# E106.net
KiCad netlist of a schematic drawn in EAGLE
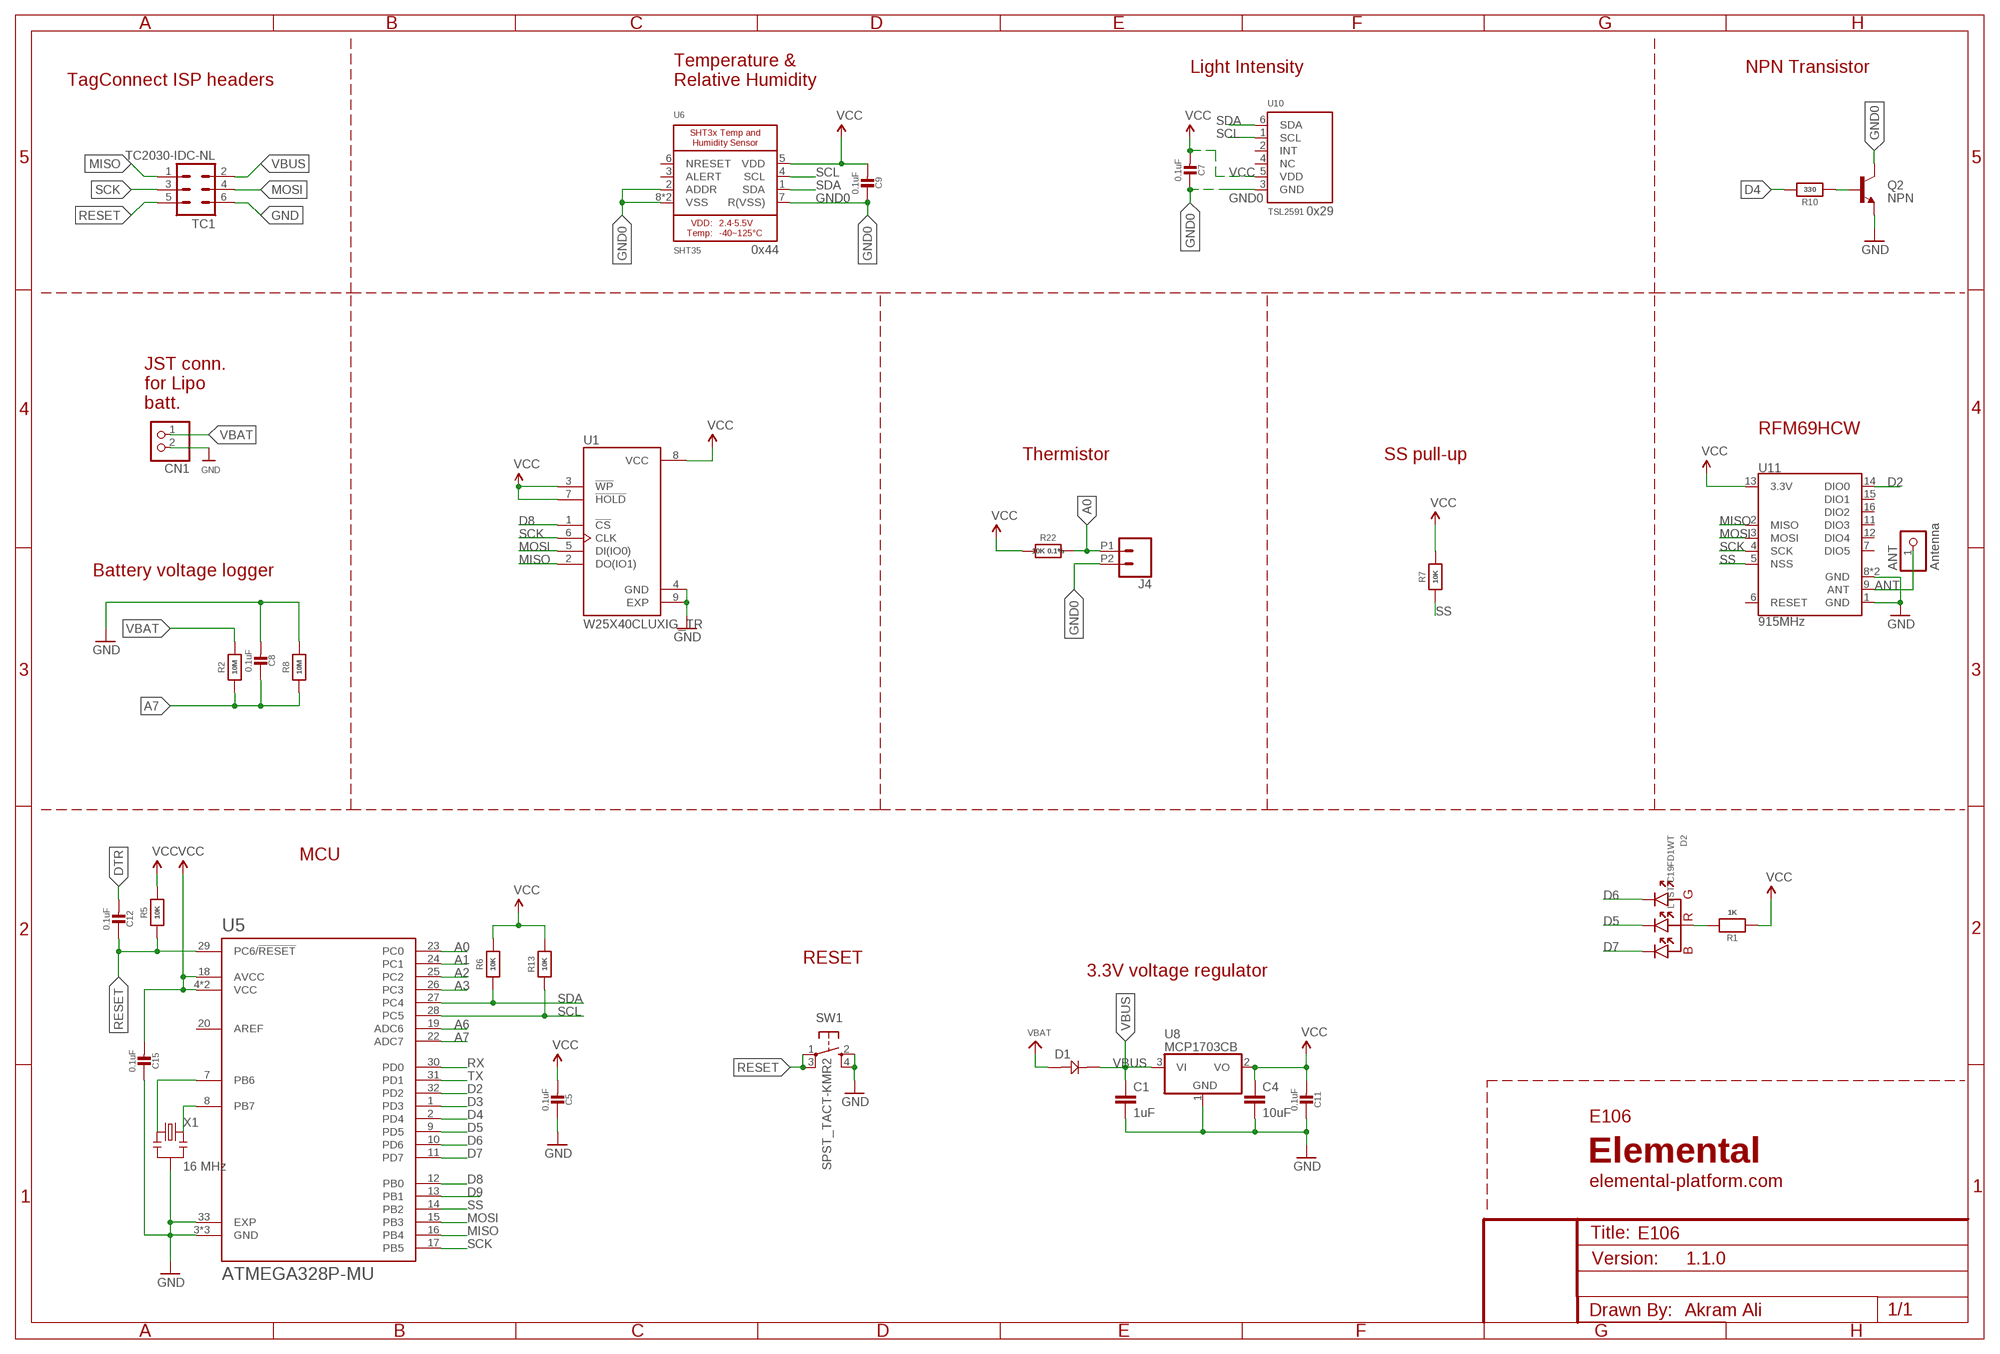
[diagram p0: schematic, sheet 1]

(export (version "E")
  (design (tool "Eeschema 10.0.6"))
  (components
    (comp (ref "ANT")
      (value "Antenna")
      (footprint "eagle-import:1X01-CLEANBIG")
      (fields (field (name "MPN") "Helical antenna"))
      (libsource (lib "eagle-import") (part "PINHD-1X1CB"))
    )
    (comp (ref "C1")
      (value "1uF")
      (footprint "eagle-import:0805")
      (fields (field (name "MPN") "CC0805ZRY5V8BB105"))
      (libsource (lib "eagle-import") (part "CAP0805"))
    )
    (comp (ref "C4")
      (value "10uF")
      (footprint "eagle-import:0805")
      (fields (field (name "MPN") "CC0805KKX5R6BB106"))
      (libsource (lib "eagle-import") (part "CAP0805"))
    )
    (comp (ref "C5")
      (value "0.1uF")
      (footprint "eagle-import:MICROBUILDER__0402MP")
      (fields (field (name "MPN") "GRM155R71C104KA88J"))
      (libsource (lib "eagle-import") (part "MICROBUILDER_CAP_CERAMIC_0402MP"))
    )
    (comp (ref "C7")
      (value "0.1uF")
      (footprint "eagle-import:MICROBUILDER__0402MP")
      (fields (field (name "MPN") "GRM155R71C104KA88J"))
      (libsource (lib "eagle-import") (part "MICROBUILDER_CAP_CERAMIC_0402MP"))
    )
    (comp (ref "C8")
      (value "0.1uF")
      (footprint "eagle-import:MICROBUILDER__0402MP")
      (fields (field (name "MPN") "GRM155R71C104KA88J"))
      (libsource (lib "eagle-import") (part "MICROBUILDER_CAP_CERAMIC_0402MP"))
    )
    (comp (ref "C9")
      (value "0.1uF")
      (footprint "eagle-import:MICROBUILDER__0402MP")
      (fields (field (name "MPN") "GRM155R71C104KA88J"))
      (libsource (lib "eagle-import") (part "MICROBUILDER_CAP_CERAMIC_0402MP"))
    )
    (comp (ref "C11")
      (value "0.1uF")
      (footprint "eagle-import:MICROBUILDER__0402MP")
      (fields (field (name "MPN") "GRM155R71C104KA88J"))
      (libsource (lib "eagle-import") (part "MICROBUILDER_CAP_CERAMIC_0402MP"))
    )
    (comp (ref "C12")
      (value "0.1uF")
      (footprint "eagle-import:MICROBUILDER__0402MP")
      (fields (field (name "MPN") "GRM155R71C104KA88J"))
      (libsource (lib "eagle-import") (part "MICROBUILDER_CAP_CERAMIC_0402MP"))
    )
    (comp (ref "C15")
      (value "0.1uF")
      (footprint "eagle-import:MICROBUILDER__0402MP")
      (fields (field (name "MPN") "GRM155R71C104KA88J"))
      (libsource (lib "eagle-import") (part "MICROBUILDER_CAP_CERAMIC_0402MP"))
    )
    (comp (ref "CN1")
      (value "JST_2PIN-SMT-RA")
      (footprint "eagle-import:JST-PH-2-SMT-RA")
      (libsource (lib "eagle-import") (part "JST_2PIN-SMT-RA"))
    )
    (comp (ref "D1")
      (value "DIODE_SCHOTTKY0805-RES")
      (footprint "eagle-import:0805")
      (libsource (lib "eagle-import") (part "DIODE_SCHOTTKY0805-RES"))
    )
    (comp (ref "D2")
      (value "LTST-C19FD1WT")
      (footprint "eagle-import:4-SMD")
      (fields (field (name "MF") "Lite-On Inc."))
      (libsource (lib "eagle-import") (part "LTST-C19FD1WT"))
    )
    (comp (ref "J4")
      (value "CONN_022.54MM_SCREWTERM")
      (footprint "eagle-import:1X02_2.54_SCREWTERM")
      (libsource (lib "eagle-import") (part "CONN_022.54MM_SCREWTERM"))
    )
    (comp (ref "Q2")
      (value "NPN")
      (footprint "eagle-import:SOT23-3@1")
      (libsource (lib "eagle-import") (part "TRANSISTOR_NPNMMBT5088"))
    )
    (comp (ref "R1")
      (value "1K")
      (footprint "eagle-import:MICROBUILDER__0402MP")
      (fields (field (name "MPN") "RC0402JR-0710KL"))
      (libsource (lib "eagle-import") (part "MICROBUILDER_RESISTOR_0402MP"))
    )
    (comp (ref "R2")
      (value "10M")
      (footprint "eagle-import:MICROBUILDER__0402MP")
      (fields (field (name "MPN") "RC0402JR-0710KL"))
      (libsource (lib "eagle-import") (part "MICROBUILDER_RESISTOR_0402MP"))
    )
    (comp (ref "R5")
      (value "10K")
      (footprint "eagle-import:MICROBUILDER__0402MP")
      (fields (field (name "MPN") "RC0402JR-0710KL"))
      (libsource (lib "eagle-import") (part "MICROBUILDER_RESISTOR_0402MP"))
    )
    (comp (ref "R6")
      (value "10K")
      (footprint "eagle-import:MICROBUILDER__0402MP")
      (fields (field (name "MPN") "RC0402JR-0710KL"))
      (libsource (lib "eagle-import") (part "MICROBUILDER_RESISTOR_0402MP"))
    )
    (comp (ref "R7")
      (value "10K")
      (footprint "eagle-import:MICROBUILDER__0402MP")
      (fields (field (name "MPN") "RC0402JR-0710KL"))
      (libsource (lib "eagle-import") (part "MICROBUILDER_RESISTOR_0402MP"))
    )
    (comp (ref "R8")
      (value "10M")
      (footprint "eagle-import:MICROBUILDER__0402MP")
      (fields (field (name "MPN") "RC0402JR-0710KL"))
      (libsource (lib "eagle-import") (part "MICROBUILDER_RESISTOR_0402MP"))
    )
    (comp (ref "R10")
      (value "330")
      (footprint "eagle-import:MICROBUILDER__0402MP")
      (fields (field (name "MPN") "RC0402JR-0710KL"))
      (libsource (lib "eagle-import") (part "MICROBUILDER_RESISTOR_0402MP"))
    )
    (comp (ref "R13")
      (value "10K")
      (footprint "eagle-import:MICROBUILDER__0402MP")
      (fields (field (name "MPN") "RC0402JR-0710KL"))
      (libsource (lib "eagle-import") (part "MICROBUILDER_RESISTOR_0402MP"))
    )
    (comp (ref "R22")
      (value "10K 0.1%")
      (footprint "eagle-import:MICROBUILDER__0402MP")
      (fields (field (name "MPN") "RC0402JR-0727RL"))
      (libsource (lib "eagle-import") (part "MICROBUILDER_RESISTOR_0402MP"))
    )
    (comp (ref "SW1")
      (value "SPST_TACT-KMR2")
      (footprint "eagle-import:KMR2")
      (libsource (lib "eagle-import") (part "SPST_TACT-KMR2"))
    )
    (comp (ref "TC1")
      (value "TC2030-IDC-NL")
      (footprint "eagle-import:TC2030-IDC-NL")
      (libsource (lib "eagle-import") (part "TC2030-IDC-NL"))
    )
    (comp (ref "U1")
      (value "W25X40CLUXIG_TR")
      (footprint "eagle-import:PSON50P300X200X60-9N")
      (fields
        (field (name "DIGI-KEY_PART_NUMBER") "W25X40CLUXIGCT-ND")
        (field (name "MF") "Winbond Electronics")
        (field (name "MP") "W25X40CLUXIG TR")
      )
      (libsource (lib "eagle-import") (part "W25X40CLUXIG_TR"))
    )
    (comp (ref "U5")
      (value "ATMEGA328P-MU")
      (footprint "eagle-import:QFN50P500X500X100-33N")
      (fields (field (name "MF") "Atmel"))
      (libsource (lib "eagle-import") (part "ATMEGA328P-MU"))
    )
    (comp (ref "U6")
      (value "SHT35")
      (footprint "eagle-import:SHT3X")
      (fields (field (name "MPN") "SHT35-DIS-B"))
      (libsource (lib "eagle-import") (part "SHT3X"))
    )
    (comp (ref "U8")
      (value "MCP1703CB")
      (footprint "eagle-import:SOT23")
      (fields (field (name "MPN") "MCP1703T-3302E/CB"))
      (libsource (lib "eagle-import") (part "MCP1703CB"))
    )
    (comp (ref "U10")
      (value "TSL2591")
      (footprint "eagle-import:DFN6_TAOS")
      (fields (field (name "MPN") "TSL25911FN "))
      (libsource (lib "eagle-import") (part "LIGHT_TSL2591"))
    )
    (comp (ref "U11")
      (value "915MHz")
      (footprint "eagle-import:RFM69HCW-XXXS2")
      (fields (field (name "MPN") "RFM69HCW"))
      (libsource (lib "eagle-import") (part "RFM69HCW-915"))
    )
    (comp (ref "X1")
      (value "16 MHz")
      (footprint "eagle-import:RESONATOR-SMD")
      (fields (field (name "MPN") "CSTCE16M0V53-R0"))
      (libsource (lib "eagle-import") (part "RESONATORSMD"))
    )
  )
  (nets
    (net (code "1") (name "/A1") (class "Default")
      (node (ref "U5") (pin "24") (pinfunction "PC1_24") (pintype "bidirectional"))
    )
    (net (code "2") (name "/A2") (class "Default")
      (node (ref "U5") (pin "25") (pinfunction "PC2_25") (pintype "bidirectional"))
    )
    (net (code "3") (name "/A3") (class "Default")
      (node (ref "U5") (pin "26") (pinfunction "PC3_26") (pintype "bidirectional"))
    )
    (net (code "4") (name "/A6") (class "Default")
      (node (ref "U5") (pin "19") (pinfunction "ADC6_19") (pintype "bidirectional"))
    )
    (net (code "5") (name "/ANT") (class "Default")
      (node (ref "ANT") (pin "1") (pinfunction "1_1") (pintype "passive"))
      (node (ref "U11") (pin "9") (pinfunction "ANT_9") (pintype "passive"))
    )
    (net (code "6") (name "/D2") (class "Default")
      (node (ref "U11") (pin "14") (pinfunction "DIO0_14") (pintype "bidirectional"))
      (node (ref "U5") (pin "32") (pinfunction "PD2_32") (pintype "bidirectional"))
    )
    (net (code "7") (name "/D3") (class "Default")
      (node (ref "U5") (pin "1") (pinfunction "PD3_1") (pintype "bidirectional"))
    )
    (net (code "8") (name "/D5") (class "Default")
      (node (ref "D2") (pin "2") (pinfunction "C2_2") (pintype "bidirectional"))
      (node (ref "U5") (pin "9") (pinfunction "PD5_9") (pintype "bidirectional"))
    )
    (net (code "9") (name "/D6") (class "Default")
      (node (ref "D2") (pin "3") (pinfunction "C3_3") (pintype "bidirectional"))
      (node (ref "U5") (pin "10") (pinfunction "PD6_10") (pintype "bidirectional"))
    )
    (net (code "10") (name "/D7") (class "Default")
      (node (ref "D2") (pin "1") (pinfunction "C1_1") (pintype "bidirectional"))
      (node (ref "U5") (pin "11") (pinfunction "PD7_11") (pintype "bidirectional"))
    )
    (net (code "11") (name "/D8") (class "Default")
      (node (ref "U1") (pin "1") (pinfunction "~{CS}_1") (pintype "input"))
      (node (ref "U5") (pin "12") (pinfunction "PB0_12") (pintype "bidirectional"))
    )
    (net (code "12") (name "/D9") (class "Default")
      (node (ref "U5") (pin "13") (pinfunction "PB1_13") (pintype "bidirectional"))
    )
    (net (code "13") (name "/RX") (class "Default")
      (node (ref "U5") (pin "30") (pinfunction "PD0_30") (pintype "bidirectional"))
    )
    (net (code "14") (name "/SCL") (class "Default")
      (node (ref "R13") (pin "1") (pinfunction "1_1") (pintype "passive"))
      (node (ref "U10") (pin "1") (pinfunction "SCL_1") (pintype "bidirectional"))
      (node (ref "U5") (pin "28") (pinfunction "PC5_28") (pintype "bidirectional"))
      (node (ref "U6") (pin "4") (pinfunction "SCL_4") (pintype "bidirectional"))
    )
    (net (code "15") (name "/SDA") (class "Default")
      (node (ref "R6") (pin "1") (pinfunction "1_1") (pintype "passive"))
      (node (ref "U10") (pin "6") (pinfunction "SDA_6") (pintype "bidirectional"))
      (node (ref "U5") (pin "27") (pinfunction "PC4_27") (pintype "bidirectional"))
      (node (ref "U6") (pin "1") (pinfunction "SDA_1") (pintype "bidirectional"))
    )
    (net (code "16") (name "/SS") (class "Default")
      (node (ref "R7") (pin "1") (pinfunction "1_1") (pintype "passive"))
      (node (ref "U11") (pin "5") (pinfunction "NSS_5") (pintype "input"))
      (node (ref "U5") (pin "14") (pinfunction "PB2_14") (pintype "bidirectional"))
    )
    (net (code "17") (name "/TX") (class "Default")
      (node (ref "U5") (pin "31") (pinfunction "PD1_31") (pintype "bidirectional"))
    )
    (net (code "18") (name "A0") (class "Default")
      (node (ref "J4") (pin "P1") (pinfunction "1_P1") (pintype "passive"))
      (node (ref "R22") (pin "2") (pinfunction "2_2") (pintype "passive"))
      (node (ref "U5") (pin "23") (pinfunction "PC0_23") (pintype "bidirectional"))
    )
    (net (code "19") (name "A7") (class "Default")
      (node (ref "C8") (pin "1") (pinfunction "1_1") (pintype "passive"))
      (node (ref "R2") (pin "1") (pinfunction "1_1") (pintype "passive"))
      (node (ref "R8") (pin "1") (pinfunction "1_1") (pintype "passive"))
      (node (ref "U5") (pin "22") (pinfunction "ADC7_22") (pintype "bidirectional"))
    )
    (net (code "20") (name "D4") (class "Default")
      (node (ref "R10") (pin "2") (pinfunction "2_2") (pintype "passive"))
      (node (ref "U5") (pin "2") (pinfunction "PD4_2") (pintype "bidirectional"))
    )
    (net (code "21") (name "DTR") (class "Default")
      (node (ref "C12") (pin "2") (pinfunction "2_2") (pintype "passive"))
    )
    (net (code "22") (name "GND") (class "Default")
      (node (ref "C1") (pin "2") (pinfunction "2_2") (pintype "passive"))
      (node (ref "C11") (pin "1") (pinfunction "1_1") (pintype "passive"))
      (node (ref "C15") (pin "1") (pinfunction "1_1") (pintype "passive"))
      (node (ref "C4") (pin "2") (pinfunction "2_2") (pintype "passive"))
      (node (ref "C5") (pin "1") (pinfunction "1_1") (pintype "passive"))
      (node (ref "C8") (pin "2") (pinfunction "2_2") (pintype "passive"))
      (node (ref "CN1") (pin "2") (pinfunction "1_2") (pintype "passive"))
      (node (ref "Q2") (pin "2") (pinfunction "E_2") (pintype "passive"))
      (node (ref "R8") (pin "2") (pinfunction "2_2") (pintype "passive"))
      (node (ref "SW1") (pin "2") (pinfunction "S_2") (pintype "passive"))
      (node (ref "SW1") (pin "4") (pinfunction "S1_4") (pintype "passive"))
      (node (ref "TC1") (pin "6") (pinfunction "6_6") (pintype "passive"))
      (node (ref "U1") (pin "4") (pinfunction "GND_4") (pintype "power_in"))
      (node (ref "U1") (pin "9") (pinfunction "EXP_9") (pintype "power_in"))
      (node (ref "U11") (pin "1") (pinfunction "GND_1") (pintype "power_in"))
      (node (ref "U11") (pin "10") (pinfunction "GND_10") (pintype "power_in"))
      (node (ref "U11") (pin "8") (pinfunction "GND_8") (pintype "power_in"))
      (node (ref "U5") (pin "21") (pinfunction "GND_21") (pintype "power_in"))
      (node (ref "U5") (pin "3") (pinfunction "GND_3") (pintype "power_in"))
      (node (ref "U5") (pin "33") (pinfunction "EXP_33") (pintype "power_in"))
      (node (ref "U5") (pin "5") (pinfunction "GND_5") (pintype "power_in"))
      (node (ref "U8") (pin "1") (pinfunction "GND_1") (pintype "passive"))
      (node (ref "X1") (pin "2") (pinfunction "2_2") (pintype "passive"))
    )
    (net (code "23") (name "GND0") (class "Default")
      (node (ref "C7") (pin "1") (pinfunction "1_1") (pintype "passive"))
      (node (ref "C9") (pin "1") (pinfunction "1_1") (pintype "passive"))
      (node (ref "J4") (pin "P2") (pinfunction "2_P2") (pintype "passive"))
      (node (ref "Q2") (pin "3") (pinfunction "C_3") (pintype "passive"))
      (node (ref "U10") (pin "3") (pinfunction "GND_3") (pintype "power_in"))
      (node (ref "U6") (pin "2") (pinfunction "ADDR_2") (pintype "bidirectional"))
      (node (ref "U6") (pin "7") (pinfunction "R(VSS)_7") (pintype "bidirectional"))
      (node (ref "U6") (pin "8") (pinfunction "VSS_8") (pintype "power_in"))
      (node (ref "U6") (pin "THERMAL") (pinfunction "VSS_THERMAL") (pintype "power_in"))
    )
    (net (code "24") (name "MISO") (class "Default")
      (node (ref "TC1") (pin "1") (pinfunction "1_1") (pintype "passive"))
      (node (ref "U1") (pin "2") (pinfunction "DO(IO1)_2") (pintype "bidirectional"))
      (node (ref "U11") (pin "2") (pinfunction "MISO_2") (pintype "bidirectional"))
      (node (ref "U5") (pin "16") (pinfunction "PB4_16") (pintype "bidirectional"))
    )
    (net (code "25") (name "MOSI") (class "Default")
      (node (ref "TC1") (pin "4") (pinfunction "4_4") (pintype "passive"))
      (node (ref "U1") (pin "5") (pinfunction "DI(IO0)_5") (pintype "bidirectional"))
      (node (ref "U11") (pin "3") (pinfunction "MOSI_3") (pintype "input"))
      (node (ref "U5") (pin "15") (pinfunction "PB3_15") (pintype "bidirectional"))
    )
    (net (code "26") (name "Net-(D2-A)") (class "Default")
      (node (ref "D2") (pin "4") (pinfunction "A_4") (pintype "bidirectional"))
      (node (ref "R1") (pin "2") (pinfunction "2_2") (pintype "passive"))
    )
    (net (code "27") (name "Net-(Q2-B)") (class "Default")
      (node (ref "Q2") (pin "1") (pinfunction "B_1") (pintype "passive"))
      (node (ref "R10") (pin "1") (pinfunction "1_1") (pintype "passive"))
    )
    (net (code "28") (name "Net-(U5-PB6)") (class "Default")
      (node (ref "U5") (pin "7") (pinfunction "PB6_7") (pintype "bidirectional"))
      (node (ref "X1") (pin "1") (pinfunction "1_1") (pintype "passive"))
    )
    (net (code "29") (name "Net-(U5-PB7)") (class "Default")
      (node (ref "U5") (pin "8") (pinfunction "PB7_8") (pintype "bidirectional"))
      (node (ref "X1") (pin "3") (pinfunction "3_3") (pintype "passive"))
    )
    (net (code "30") (name "RESET") (class "Default")
      (node (ref "C12") (pin "1") (pinfunction "1_1") (pintype "passive"))
      (node (ref "R5") (pin "1") (pinfunction "1_1") (pintype "passive"))
      (node (ref "SW1") (pin "1") (pinfunction "P_1") (pintype "passive"))
      (node (ref "SW1") (pin "3") (pinfunction "P1_3") (pintype "passive"))
      (node (ref "TC1") (pin "5") (pinfunction "5_5") (pintype "passive"))
      (node (ref "U5") (pin "29") (pinfunction "PC6/~{RESET}_29") (pintype "bidirectional"))
    )
    (net (code "31") (name "SCK") (class "Default")
      (node (ref "TC1") (pin "3") (pinfunction "3_3") (pintype "passive"))
      (node (ref "U1") (pin "6") (pinfunction "CLK_6") (pintype "input"))
      (node (ref "U11") (pin "4") (pinfunction "SCK_4") (pintype "input"))
      (node (ref "U5") (pin "17") (pinfunction "PB5_17") (pintype "bidirectional"))
    )
    (net (code "32") (name "VBAT") (class "Default")
      (node (ref "CN1") (pin "1") (pinfunction "2_1") (pintype "passive"))
      (node (ref "D1") (pin "1") (pinfunction "1_1") (pintype "passive"))
      (node (ref "R2") (pin "2") (pinfunction "2_2") (pintype "passive"))
    )
    (net (code "33") (name "VBUS") (class "Default")
      (node (ref "C1") (pin "1") (pinfunction "1_1") (pintype "passive"))
      (node (ref "D1") (pin "2") (pinfunction "2_2") (pintype "passive"))
      (node (ref "TC1") (pin "2") (pinfunction "2_2") (pintype "passive"))
      (node (ref "U8") (pin "3") (pinfunction "VI_3") (pintype "input"))
    )
    (net (code "34") (name "VCC") (class "Default")
      (node (ref "C11") (pin "2") (pinfunction "2_2") (pintype "passive"))
      (node (ref "C15") (pin "2") (pinfunction "2_2") (pintype "passive"))
      (node (ref "C4") (pin "1") (pinfunction "1_1") (pintype "passive"))
      (node (ref "C5") (pin "2") (pinfunction "2_2") (pintype "passive"))
      (node (ref "C7") (pin "2") (pinfunction "2_2") (pintype "passive"))
      (node (ref "C9") (pin "2") (pinfunction "2_2") (pintype "passive"))
      (node (ref "R1") (pin "1") (pinfunction "1_1") (pintype "passive"))
      (node (ref "R13") (pin "2") (pinfunction "2_2") (pintype "passive"))
      (node (ref "R22") (pin "1") (pinfunction "1_1") (pintype "passive"))
      (node (ref "R5") (pin "2") (pinfunction "2_2") (pintype "passive"))
      (node (ref "R6") (pin "2") (pinfunction "2_2") (pintype "passive"))
      (node (ref "R7") (pin "2") (pinfunction "2_2") (pintype "passive"))
      (node (ref "U1") (pin "3") (pinfunction "~{WP}_3") (pintype "input"))
      (node (ref "U1") (pin "7") (pinfunction "~{HOLD}_7") (pintype "input"))
      (node (ref "U1") (pin "8") (pinfunction "VCC_8") (pintype "power_in"))
      (node (ref "U10") (pin "5") (pinfunction "VDD_5") (pintype "power_in"))
      (node (ref "U11") (pin "13") (pinfunction "3.3V_13") (pintype "power_in"))
      (node (ref "U5") (pin "18") (pinfunction "AVCC_18") (pintype "power_in"))
      (node (ref "U5") (pin "4") (pinfunction "VCC_4") (pintype "power_in"))
      (node (ref "U5") (pin "6") (pinfunction "VCC_6") (pintype "power_in"))
      (node (ref "U6") (pin "5") (pinfunction "VDD_5") (pintype "power_in"))
      (node (ref "U8") (pin "2") (pinfunction "VO_2") (pintype "passive"))
    )
    (net (code "35") (name "unconnected-(U5-AREF-Pad20)") (class "Default")
      (node (ref "U5") (pin "20") (pinfunction "AREF_20") (pintype "input"))
    )
    (net (code "36") (name "unconnected-(U6-ALERT-Pad3)") (class "Default")
      (node (ref "U6") (pin "3") (pinfunction "ALERT_3") (pintype "bidirectional"))
    )
    (net (code "37") (name "unconnected-(U6-NRESET-Pad6)") (class "Default")
      (node (ref "U6") (pin "6") (pinfunction "NRESET_6") (pintype "bidirectional"))
    )
    (net (code "38") (name "unconnected-(U10-INT-Pad2)") (class "Default")
      (node (ref "U10") (pin "2") (pinfunction "INT_2") (pintype "output"))
    )
    (net (code "39") (name "unconnected-(U10-NC-Pad4)") (class "Default")
      (node (ref "U10") (pin "4") (pinfunction "NC_4") (pintype "no_connect"))
    )
    (net (code "40") (name "unconnected-(U11-DIO1-Pad15)") (class "Default")
      (node (ref "U11") (pin "15") (pinfunction "DIO1_15") (pintype "bidirectional"))
    )
    (net (code "41") (name "unconnected-(U11-DIO2-Pad16)") (class "Default")
      (node (ref "U11") (pin "16") (pinfunction "DIO2_16") (pintype "bidirectional"))
    )
    (net (code "42") (name "unconnected-(U11-DIO3-Pad11)") (class "Default")
      (node (ref "U11") (pin "11") (pinfunction "DIO3_11") (pintype "bidirectional"))
    )
    (net (code "43") (name "unconnected-(U11-DIO4-Pad12)") (class "Default")
      (node (ref "U11") (pin "12") (pinfunction "DIO4_12") (pintype "bidirectional"))
    )
    (net (code "44") (name "unconnected-(U11-DIO5-Pad7)") (class "Default")
      (node (ref "U11") (pin "7") (pinfunction "DIO5_7") (pintype "bidirectional"))
    )
    (net (code "45") (name "unconnected-(U11-RESET-Pad6)") (class "Default")
      (node (ref "U11") (pin "6") (pinfunction "RESET_6") (pintype "input"))
    )
  )
)
